# FMC_MISC.net
KiCad netlist of a schematic drawn in Altium Designer
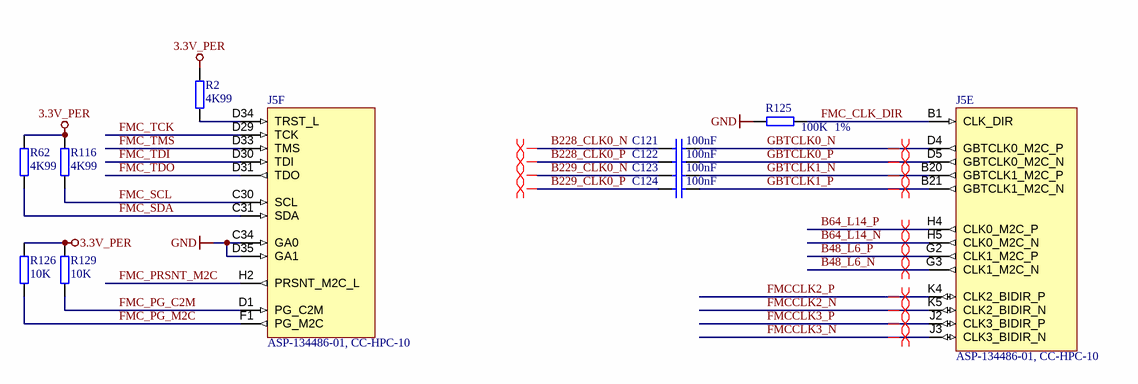
[diagram p0: FMC_MISC.SchDoc]

(export (version "E")
  (design (tool "Eeschema 10.0.6"))
  (components
    (comp (ref "C121")
      (value "100nF")
      (footprint "CAPC0603X33N")
      (description "KON 100nF 6.3V X5R SMD 10%")
      (fields (field (name "VOLTAGE") "6.3V") (field (name "TOLERANCE") "10%"))
      (libsource (lib "TE") (part "CAP-NP"))
    )
    (comp (ref "C122")
      (value "100nF")
      (footprint "CAPC0603X33N")
      (description "KON 100nF 6.3V X5R SMD 10%")
      (fields (field (name "VOLTAGE") "6.3V") (field (name "TOLERANCE") "10%"))
      (libsource (lib "TE") (part "CAP-NP"))
    )
    (comp (ref "C123")
      (value "100nF")
      (footprint "CAPC0603X33N")
      (description "KON 100nF 6.3V X5R SMD 10%")
      (fields (field (name "VOLTAGE") "6.3V") (field (name "TOLERANCE") "10%"))
      (libsource (lib "TE") (part "CAP-NP"))
    )
    (comp (ref "C124")
      (value "100nF")
      (footprint "CAPC0603X33N")
      (description "KON 100nF 6.3V X5R SMD 10%")
      (fields (field (name "VOLTAGE") "6.3V") (field (name "TOLERANCE") "10%"))
      (libsource (lib "TE") (part "CAP-NP"))
    )
    (comp (ref "J5")
      (value "ASP-134486-01, CC-HPC-10")
      (footprint "ASP-134486-01B")
      (description "ASP-134486-01 female, CC-HPC-10")
      (libsource (lib "TE") (part "VITA57-FMC-HPC-Layout"))
    )
    (comp (ref "R2")
      (value "4K99")
      (footprint "RESC1005X40N")
      (description "WID SMD 4K99 1% 0,063W")
      (fields (field (name "TOLERANCE") "1%"))
      (libsource (lib "TE") (part "RES"))
    )
    (comp (ref "R62")
      (value "4K99")
      (footprint "RESC1005X40N")
      (description "WID SMD 4K99 1% 0,063W")
      (fields (field (name "TOLERANCE") "1%"))
      (libsource (lib "TE") (part "RES"))
    )
    (comp (ref "R116")
      (value "4K99")
      (footprint "RESC1005X40N")
      (description "WID SMD 4K99 1% 0,063W")
      (fields (field (name "TOLERANCE") "1%"))
      (libsource (lib "TE") (part "RES"))
    )
    (comp (ref "R125")
      (value "100K")
      (footprint "RESC1005X40N")
      (description "WID SMD 100K 1% 0,063W")
      (fields (field (name "TOLERANCE") "1%"))
      (libsource (lib "TE") (part "RES"))
    )
    (comp (ref "R126")
      (value "10K")
      (footprint "RESC1005X40N")
      (description "WID SMD 10K 1% 0,063W")
      (fields (field (name "TOLERANCE") "1%"))
      (libsource (lib "TE") (part "RES"))
    )
    (comp (ref "R129")
      (value "10K")
      (footprint "RESC1005X40N")
      (description "WID SMD 10K 1% 0,063W")
      (fields (field (name "TOLERANCE") "1%"))
      (libsource (lib "TE") (part "RES"))
    )
  )
  (nets
    (net (code "1") (name "/B48_L6_N") (class "Default")
      (node (ref "J5") (pin "G3") (pinfunction "CLK1_M2C_N_G3") (pintype "output"))
    )
    (net (code "2") (name "/B48_L6_P") (class "Default")
      (node (ref "J5") (pin "G2") (pinfunction "CLK1_M2C_P_G2") (pintype "output"))
    )
    (net (code "3") (name "/B64_L14_N") (class "Default")
      (node (ref "J5") (pin "H5") (pinfunction "CLK0_M2C_N_H5") (pintype "output"))
    )
    (net (code "4") (name "/B64_L14_P") (class "Default")
      (node (ref "J5") (pin "H4") (pinfunction "CLK0_M2C_P_H4") (pintype "output"))
    )
    (net (code "5") (name "/B228_CLK0_N") (class "Default")
      (node (ref "C121") (pin "1") (pinfunction "1_1") (pintype "passive"))
    )
    (net (code "6") (name "/B228_CLK0_P") (class "Default")
      (node (ref "C122") (pin "1") (pinfunction "1_1") (pintype "passive"))
    )
    (net (code "7") (name "/B229_CLK0_N") (class "Default")
      (node (ref "C123") (pin "1") (pinfunction "1_1") (pintype "passive"))
    )
    (net (code "8") (name "/B229_CLK0_P") (class "Default")
      (node (ref "C124") (pin "1") (pinfunction "1_1") (pintype "passive"))
    )
    (net (code "9") (name "/FMCCLK2_N") (class "Default")
      (node (ref "J5") (pin "K5") (pinfunction "CLK2_BIDIR_N_K5") (pintype "bidirectional"))
    )
    (net (code "10") (name "/FMCCLK2_P") (class "Default")
      (node (ref "J5") (pin "K4") (pinfunction "CLK2_BIDIR_P_K4") (pintype "bidirectional"))
    )
    (net (code "11") (name "/FMCCLK3_N") (class "Default")
      (node (ref "J5") (pin "J3") (pinfunction "CLK3_BIDIR_N_J3") (pintype "bidirectional"))
    )
    (net (code "12") (name "/FMCCLK3_P") (class "Default")
      (node (ref "J5") (pin "J2") (pinfunction "CLK3_BIDIR_P_J2") (pintype "bidirectional"))
    )
    (net (code "13") (name "/FMC_CLK_DIR") (class "Default")
      (node (ref "J5") (pin "B1") (pinfunction "CLK_DIR_B1") (pintype "input"))
      (node (ref "R125") (pin "2") (pinfunction "2_2") (pintype "passive"))
    )
    (net (code "14") (name "/FMC_PG_C2M") (class "Default")
      (node (ref "J5") (pin "D1") (pinfunction "PG_C2M_D1") (pintype "input"))
      (node (ref "R129") (pin "2") (pinfunction "2_2") (pintype "passive"))
    )
    (net (code "15") (name "/FMC_PG_M2C") (class "Default")
      (node (ref "J5") (pin "F1") (pinfunction "PG_M2C_F1") (pintype "output"))
      (node (ref "R126") (pin "1") (pinfunction "1_1") (pintype "passive"))
    )
    (net (code "16") (name "/FMC_PRSNT_M2C") (class "Default")
      (node (ref "J5") (pin "H2") (pinfunction "PRSNT_M2C_L_H2") (pintype "output"))
    )
    (net (code "17") (name "/FMC_SCL") (class "Default")
      (node (ref "J5") (pin "C30") (pinfunction "SCL_C30") (pintype "input"))
      (node (ref "R116") (pin "1") (pinfunction "1_1") (pintype "passive"))
    )
    (net (code "18") (name "/FMC_SDA") (class "Default")
      (node (ref "J5") (pin "C31") (pinfunction "SDA_C31") (pintype "input"))
      (node (ref "R62") (pin "1") (pinfunction "1_1") (pintype "passive"))
    )
    (net (code "19") (name "/FMC_TCK") (class "Default")
      (node (ref "J5") (pin "D29") (pinfunction "TCK_D29") (pintype "input"))
    )
    (net (code "20") (name "/FMC_TDI") (class "Default")
      (node (ref "J5") (pin "D30") (pinfunction "TDI_D30") (pintype "input"))
    )
    (net (code "21") (name "/FMC_TDO") (class "Default")
      (node (ref "J5") (pin "D31") (pinfunction "TDO_D31") (pintype "output"))
    )
    (net (code "22") (name "/FMC_TMS") (class "Default")
      (node (ref "J5") (pin "D33") (pinfunction "TMS_D33") (pintype "input"))
    )
    (net (code "23") (name "/GBTCLK0_N") (class "Default")
      (node (ref "C121") (pin "2") (pinfunction "2_2") (pintype "passive"))
      (node (ref "J5") (pin "D4") (pinfunction "GBTCLK0_M2C_P_D4") (pintype "output"))
    )
    (net (code "24") (name "/GBTCLK0_P") (class "Default")
      (node (ref "C122") (pin "2") (pinfunction "2_2") (pintype "passive"))
      (node (ref "J5") (pin "D5") (pinfunction "GBTCLK0_M2C_N_D5") (pintype "output"))
    )
    (net (code "25") (name "/GBTCLK1_N") (class "Default")
      (node (ref "C123") (pin "2") (pinfunction "2_2") (pintype "passive"))
      (node (ref "J5") (pin "B20") (pinfunction "GBTCLK1_M2C_P_B20") (pintype "output"))
    )
    (net (code "26") (name "/GBTCLK1_P") (class "Default")
      (node (ref "C124") (pin "2") (pinfunction "2_2") (pintype "passive"))
      (node (ref "J5") (pin "B21") (pinfunction "GBTCLK1_M2C_N_B21") (pintype "output"))
    )
    (net (code "27") (name "3.3V_PER") (class "Default")
      (node (ref "R116") (pin "2") (pinfunction "2_2") (pintype "passive"))
      (node (ref "R126") (pin "2") (pinfunction "2_2") (pintype "passive"))
      (node (ref "R129") (pin "1") (pinfunction "1_1") (pintype "passive"))
      (node (ref "R2") (pin "2") (pinfunction "2_2") (pintype "passive"))
      (node (ref "R62") (pin "2") (pinfunction "2_2") (pintype "passive"))
    )
    (net (code "28") (name "GND") (class "Default")
      (node (ref "J5") (pin "C34") (pinfunction "GA0_C34") (pintype "input"))
      (node (ref "J5") (pin "D35") (pinfunction "GA1_D35") (pintype "input"))
      (node (ref "R125") (pin "1") (pinfunction "1_1") (pintype "passive"))
    )
    (net (code "29") (name "Net-(J5F-TRST_L)") (class "Default")
      (node (ref "J5") (pin "D34") (pinfunction "TRST_L_D34") (pintype "input"))
      (node (ref "R2") (pin "1") (pinfunction "1_1") (pintype "passive"))
    )
  )
)
